# Analog_In.net
KiCad netlist of a schematic drawn in Altium Designer
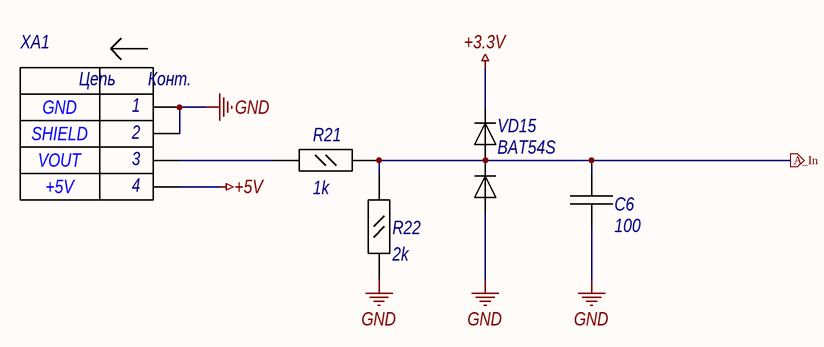
[diagram p0: Analog_In.SchDoc]

(export (version "E")
  (design (tool "Eeschema 10.0.6"))
  (components
    (comp (ref "C6")
      (value "100")
      (footprint "0805")
      (fields (field (name "MANUFACTURER") "YAGEO"))
      (libsource (lib "DX_test_lib2") (part "CC0805"))
    )
    (comp (ref "R21")
      (value "1k")
      (footprint "0805")
      (description "Резистор общего назначения 5%")
      (fields (field (name "MANUFACTURER") "YAGEO"))
      (libsource (lib "DX_test_lib2") (part "RC0805JR"))
    )
    (comp (ref "R22")
      (value "2k")
      (footprint "0805")
      (description "Резистор общего назначения 5%")
      (fields (field (name "MANUFACTURER") "YAGEO"))
      (libsource (lib "DX_test_lib2") (part "RC0805JR"))
    )
    (comp (ref "VD15")
      (value "BAT54S")
      (footprint "SOT-23")
      (description "Диоды Шотки")
      (fields (field (name "MANUFACTURER") "NXP"))
      (libsource (lib "Diodes") (part "BAT54S"))
    )
    (comp (ref "XA1")
      (value "CWF-4")
      (footprint "CWF-4")
      (description "Разъем питания, шаг 2.5мм")
      (libsource (lib "DX_test_lib2") (part "CWF-4"))
    )
  )
  (nets
    (net (code "1") (name "+3.3V") (class "Default")
      (node (ref "VD15") (pin "2") (pinfunction "K_2") (pintype "passive"))
    )
    (net (code "2") (name "+5V") (class "Default")
      (node (ref "XA1") (pin "4") (pinfunction "4_4") (pintype "passive"))
    )
    (net (code "3") (name "/A_In") (class "Default")
      (node (ref "C6") (pin "1") (pinfunction "1_1") (pintype "passive"))
      (node (ref "R21") (pin "2") (pinfunction "2_2") (pintype "passive"))
      (node (ref "R22") (pin "2") (pinfunction "2_2") (pintype "passive"))
      (node (ref "VD15") (pin "3") (pinfunction "AK_3") (pintype "passive"))
    )
    (net (code "4") (name "GND") (class "Default")
      (node (ref "C6") (pin "2") (pinfunction "2_2") (pintype "passive"))
      (node (ref "R22") (pin "1") (pinfunction "1_1") (pintype "passive"))
      (node (ref "VD15") (pin "1") (pinfunction "A_1") (pintype "passive"))
      (node (ref "XA1") (pin "1") (pinfunction "1_1") (pintype "passive"))
      (node (ref "XA1") (pin "2") (pinfunction "2_2") (pintype "passive"))
    )
    (net (code "5") (name "Net-(R21-Pad1)") (class "Default")
      (node (ref "R21") (pin "1") (pinfunction "1_1") (pintype "passive"))
      (node (ref "XA1") (pin "3") (pinfunction "3_3") (pintype "passive"))
    )
  )
)
